# SHIELD_ENC28J60.net
KiCad netlist of a schematic drawn in Altium Designer
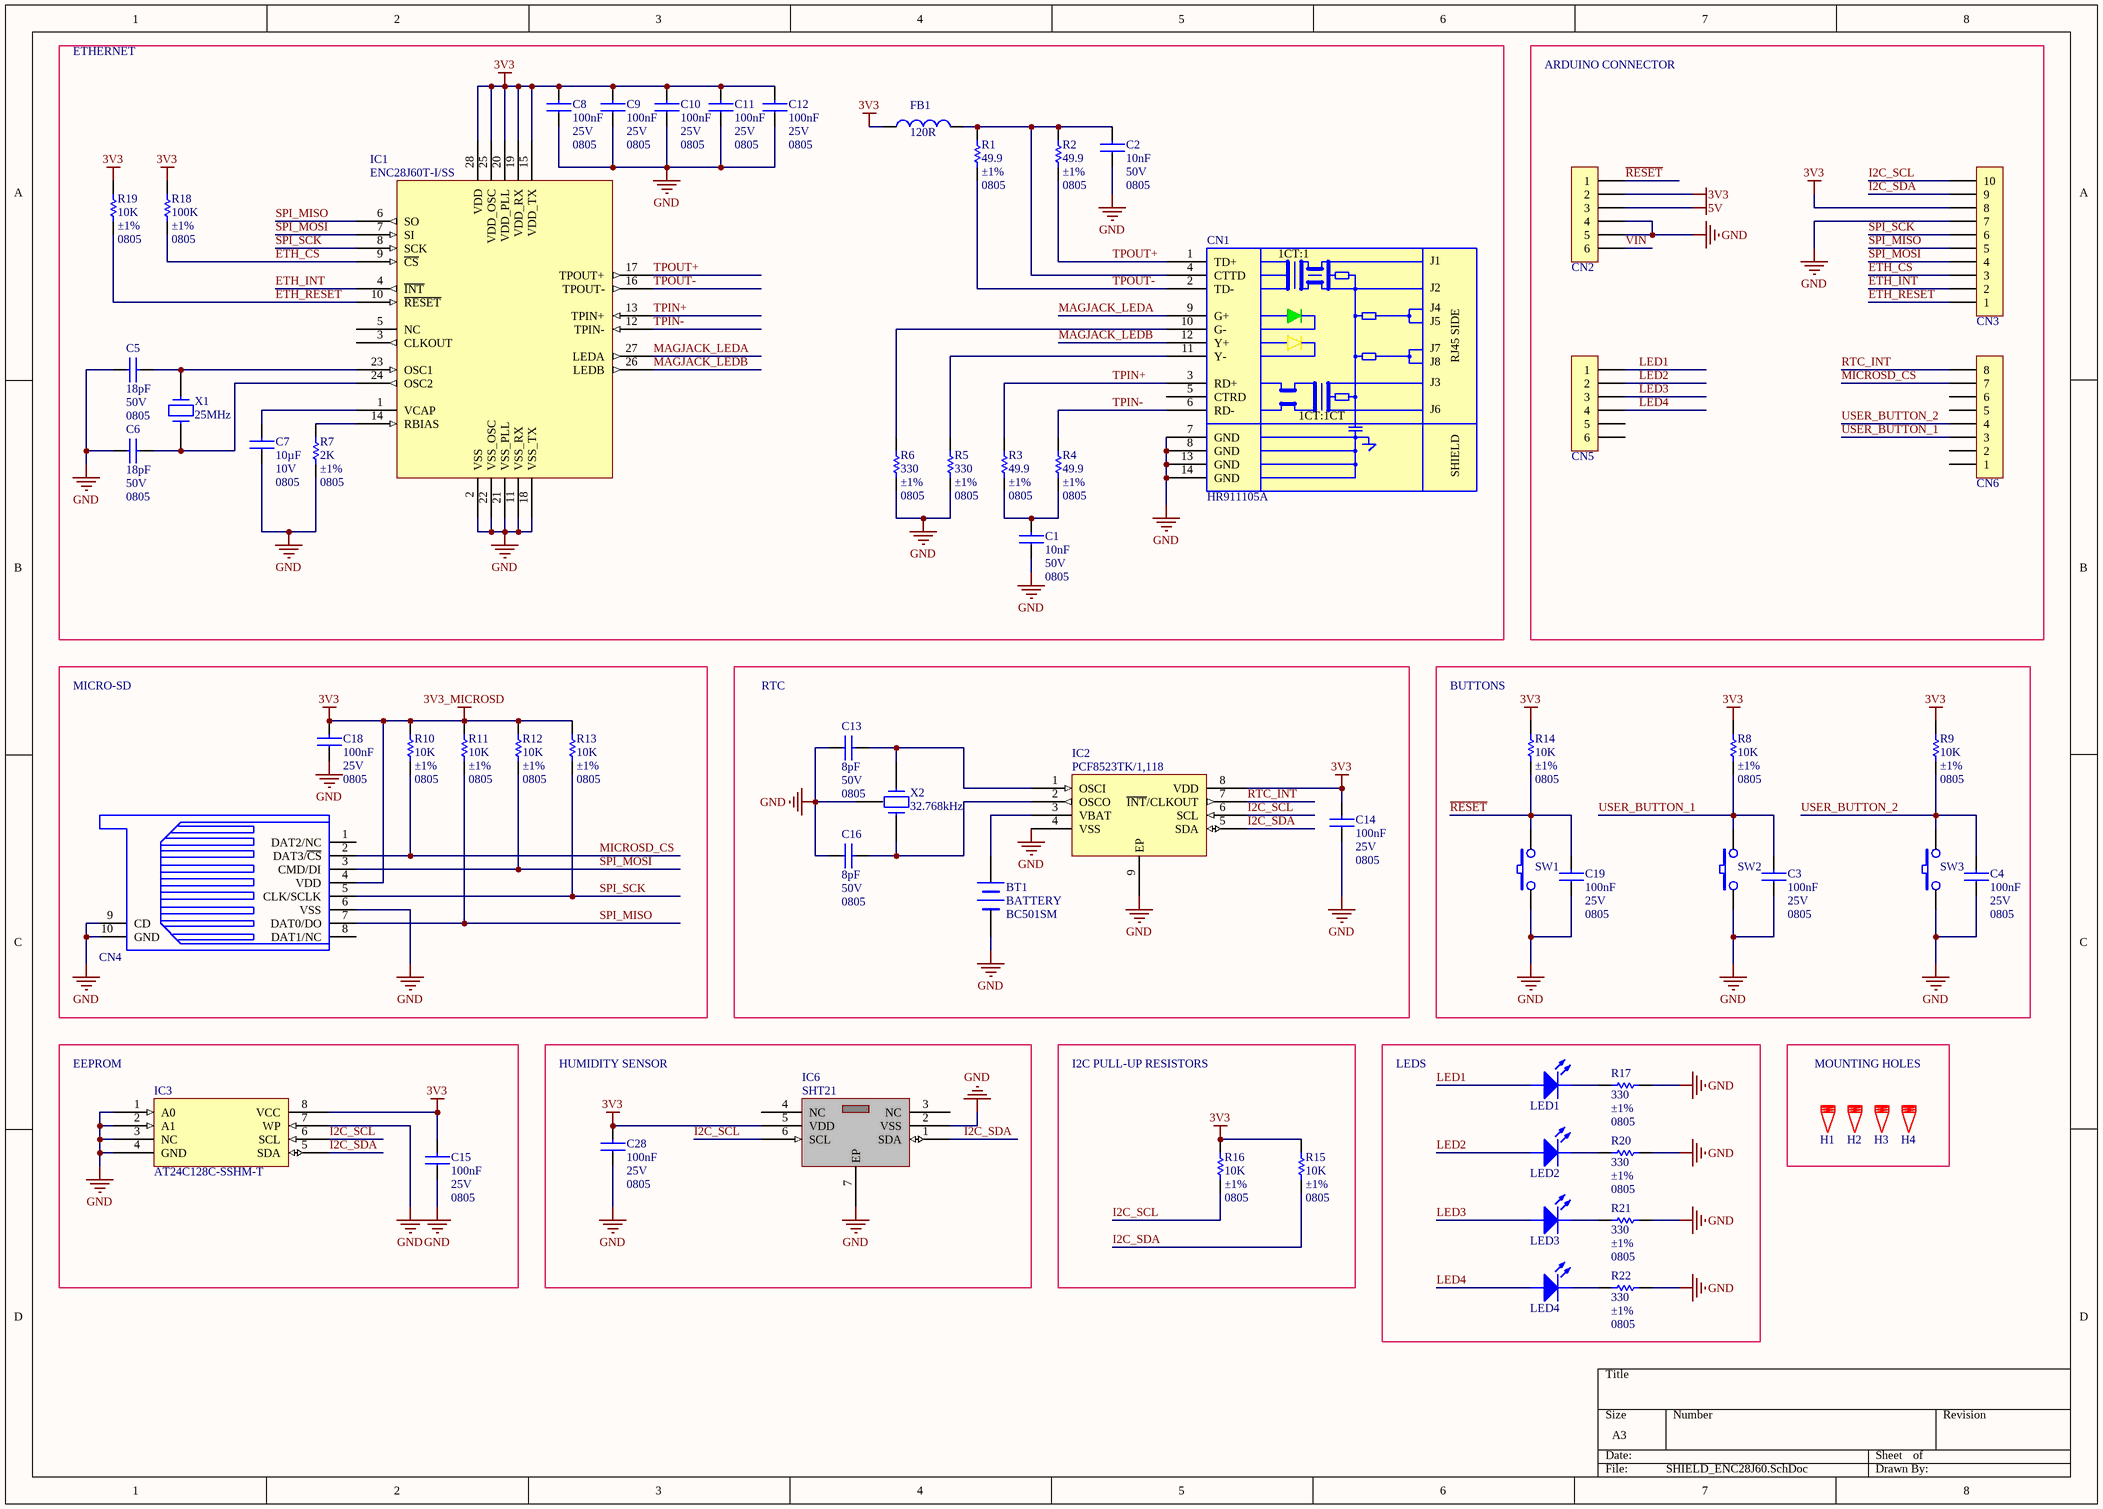
[diagram p0: SHIELD_ENC28J60.SchDoc]

(export (version "E")
  (design (tool "Eeschema 10.0.6"))
  (components
    (comp (ref "BT1")
      (value "BATTERY")
      (footprint "MPD_BC501SM")
      (description "HOLDER COIN CELL FOR CR1220 SMD")
      (fields
        (field (name "PART NUMBER") "SBAT00011")
        (field (name "MANUFACTURER PART NUMBER") "BC501SM")
        (field (name "VOLTAGE") "3V")
      )
      (libsource (lib "ComponentDatabase") (part "BATTERY"))
    )
    (comp (ref "C1")
      (value "CAP_NP")
      (footprint "CAPC2012X100N_EIA0805")
      (description "CAP CER 10000PF 50V X7R 0805")
      (fields
        (field (name "PART NUMBER") "SCAP00300085")
        (field (name "CAPACITANCE") "10nF")
        (field (name "VOLTAGE - RATED") "50V")
        (field (name "PACKAGE / CASE") "0805")
        (field (name "TOLERANCE") "±10%")
      )
      (libsource (lib "ComponentDatabase") (part "CAP_NP"))
    )
    (comp (ref "C2")
      (value "CAP_NP")
      (footprint "CAPC2012X100N_EIA0805")
      (description "CAP CER 10000PF 50V X7R 0805")
      (fields
        (field (name "PART NUMBER") "SCAP00300085")
        (field (name "CAPACITANCE") "10nF")
        (field (name "VOLTAGE - RATED") "50V")
        (field (name "PACKAGE / CASE") "0805")
        (field (name "TOLERANCE") "±10%")
      )
      (libsource (lib "ComponentDatabase") (part "CAP_NP"))
    )
    (comp (ref "C3")
      (value "CAP_NP")
      (footprint "CAPC2012X100N_EIA0805")
      (description "CAP CER 0.1UF 25V X7R 0805")
      (fields
        (field (name "PART NUMBER") "SCAP00300093")
        (field (name "CAPACITANCE") "100nF")
        (field (name "VOLTAGE - RATED") "25V")
        (field (name "PACKAGE / CASE") "0805")
        (field (name "TOLERANCE") "±10%")
      )
      (libsource (lib "ComponentDatabase") (part "CAP_NP"))
    )
    (comp (ref "C4")
      (value "CAP_NP")
      (footprint "CAPC2012X100N_EIA0805")
      (description "CAP CER 0.1UF 25V X7R 0805")
      (fields
        (field (name "PART NUMBER") "SCAP00300093")
        (field (name "CAPACITANCE") "100nF")
        (field (name "VOLTAGE - RATED") "25V")
        (field (name "PACKAGE / CASE") "0805")
        (field (name "TOLERANCE") "±10%")
      )
      (libsource (lib "ComponentDatabase") (part "CAP_NP"))
    )
    (comp (ref "C5")
      (value "CAP_NP")
      (footprint "CAPC2012X100N_EIA0805")
      (description "CAP CER 18PF 50V NP0 0805")
      (fields
        (field (name "PART NUMBER") "SCAP00300040")
        (field (name "CAPACITANCE") "18pF")
        (field (name "VOLTAGE - RATED") "50V")
        (field (name "PACKAGE / CASE") "0805")
        (field (name "TOLERANCE") "±5%")
      )
      (libsource (lib "ComponentDatabase") (part "CAP_NP"))
    )
    (comp (ref "C6")
      (value "CAP_NP")
      (footprint "CAPC2012X100N_EIA0805")
      (description "CAP CER 18PF 50V NP0 0805")
      (fields
        (field (name "PART NUMBER") "SCAP00300040")
        (field (name "CAPACITANCE") "18pF")
        (field (name "VOLTAGE - RATED") "50V")
        (field (name "PACKAGE / CASE") "0805")
        (field (name "TOLERANCE") "±5%")
      )
      (libsource (lib "ComponentDatabase") (part "CAP_NP"))
    )
    (comp (ref "C7")
      (value "CAP_NP")
      (footprint "CAPC2012X100N_EIA0805")
      (description "CAP CER 10UF 10V X5R 0805")
      (fields
        (field (name "PART NUMBER") "SCAP00300106")
        (field (name "CAPACITANCE") "10µF")
        (field (name "VOLTAGE - RATED") "10V")
        (field (name "PACKAGE / CASE") "0805")
        (field (name "TOLERANCE") "±10%")
      )
      (libsource (lib "ComponentDatabase") (part "CAP_NP"))
    )
    (comp (ref "C8")
      (value "CAP_NP")
      (footprint "CAPC2012X100N_EIA0805")
      (description "CAP CER 0.1UF 25V X7R 0805")
      (fields
        (field (name "PART NUMBER") "SCAP00300093")
        (field (name "CAPACITANCE") "100nF")
        (field (name "VOLTAGE - RATED") "25V")
        (field (name "PACKAGE / CASE") "0805")
        (field (name "TOLERANCE") "±10%")
      )
      (libsource (lib "ComponentDatabase") (part "CAP_NP"))
    )
    (comp (ref "C9")
      (value "CAP_NP")
      (footprint "CAPC2012X100N_EIA0805")
      (description "CAP CER 0.1UF 25V X7R 0805")
      (fields
        (field (name "PART NUMBER") "SCAP00300093")
        (field (name "CAPACITANCE") "100nF")
        (field (name "VOLTAGE - RATED") "25V")
        (field (name "PACKAGE / CASE") "0805")
        (field (name "TOLERANCE") "±10%")
      )
      (libsource (lib "ComponentDatabase") (part "CAP_NP"))
    )
    (comp (ref "C10")
      (value "CAP_NP")
      (footprint "CAPC2012X100N_EIA0805")
      (description "CAP CER 0.1UF 25V X7R 0805")
      (fields
        (field (name "PART NUMBER") "SCAP00300093")
        (field (name "CAPACITANCE") "100nF")
        (field (name "VOLTAGE - RATED") "25V")
        (field (name "PACKAGE / CASE") "0805")
        (field (name "TOLERANCE") "±10%")
      )
      (libsource (lib "ComponentDatabase") (part "CAP_NP"))
    )
    (comp (ref "C11")
      (value "CAP_NP")
      (footprint "CAPC2012X100N_EIA0805")
      (description "CAP CER 0.1UF 25V X7R 0805")
      (fields
        (field (name "PART NUMBER") "SCAP00300093")
        (field (name "CAPACITANCE") "100nF")
        (field (name "VOLTAGE - RATED") "25V")
        (field (name "PACKAGE / CASE") "0805")
        (field (name "TOLERANCE") "±10%")
      )
      (libsource (lib "ComponentDatabase") (part "CAP_NP"))
    )
    (comp (ref "C12")
      (value "CAP_NP")
      (footprint "CAPC2012X100N_EIA0805")
      (description "CAP CER 0.1UF 25V X7R 0805")
      (fields
        (field (name "PART NUMBER") "SCAP00300093")
        (field (name "CAPACITANCE") "100nF")
        (field (name "VOLTAGE - RATED") "25V")
        (field (name "PACKAGE / CASE") "0805")
        (field (name "TOLERANCE") "±10%")
      )
      (libsource (lib "ComponentDatabase") (part "CAP_NP"))
    )
    (comp (ref "C13")
      (value "CAP_NP")
      (footprint "CAPC2012X100N_EIA0805")
      (description "CAP CER 8PF 50V NP0 0805")
      (fields
        (field (name "PART NUMBER") "SCAP00300030")
        (field (name "CAPACITANCE") "8pF")
        (field (name "VOLTAGE - RATED") "50V")
        (field (name "PACKAGE / CASE") "0805")
        (field (name "TOLERANCE") "±0.25pF")
      )
      (libsource (lib "ComponentDatabase") (part "CAP_NP"))
    )
    (comp (ref "C14")
      (value "CAP_NP")
      (footprint "CAPC2012X100N_EIA0805")
      (description "CAP CER 0.1UF 25V X7R 0805")
      (fields
        (field (name "PART NUMBER") "SCAP00300093")
        (field (name "CAPACITANCE") "100nF")
        (field (name "VOLTAGE - RATED") "25V")
        (field (name "PACKAGE / CASE") "0805")
        (field (name "TOLERANCE") "±10%")
      )
      (libsource (lib "ComponentDatabase") (part "CAP_NP"))
    )
    (comp (ref "C15")
      (value "CAP_NP")
      (footprint "CAPC2012X100N_EIA0805")
      (description "CAP CER 0.1UF 25V X7R 0805")
      (fields
        (field (name "PART NUMBER") "SCAP00300093")
        (field (name "CAPACITANCE") "100nF")
        (field (name "VOLTAGE - RATED") "25V")
        (field (name "PACKAGE / CASE") "0805")
        (field (name "TOLERANCE") "±10%")
      )
      (libsource (lib "ComponentDatabase") (part "CAP_NP"))
    )
    (comp (ref "C16")
      (value "CAP_NP")
      (footprint "CAPC2012X100N_EIA0805")
      (description "CAP CER 8PF 50V NP0 0805")
      (fields
        (field (name "PART NUMBER") "SCAP00300030")
        (field (name "CAPACITANCE") "8pF")
        (field (name "VOLTAGE - RATED") "50V")
        (field (name "PACKAGE / CASE") "0805")
        (field (name "TOLERANCE") "±0.25pF")
      )
      (libsource (lib "ComponentDatabase") (part "CAP_NP"))
    )
    (comp (ref "C18")
      (value "CAP_NP")
      (footprint "CAPC2012X100N_EIA0805")
      (description "CAP CER 0.1UF 25V X7R 0805")
      (fields
        (field (name "PART NUMBER") "SCAP00300093")
        (field (name "CAPACITANCE") "100nF")
        (field (name "VOLTAGE - RATED") "25V")
        (field (name "PACKAGE / CASE") "0805")
        (field (name "TOLERANCE") "±10%")
      )
      (libsource (lib "ComponentDatabase") (part "CAP_NP"))
    )
    (comp (ref "C19")
      (value "CAP_NP")
      (footprint "CAPC2012X100N_EIA0805")
      (description "CAP CER 0.1UF 25V X7R 0805")
      (fields
        (field (name "PART NUMBER") "SCAP00300093")
        (field (name "CAPACITANCE") "100nF")
        (field (name "VOLTAGE - RATED") "25V")
        (field (name "PACKAGE / CASE") "0805")
        (field (name "TOLERANCE") "±10%")
      )
      (libsource (lib "ComponentDatabase") (part "CAP_NP"))
    )
    (comp (ref "C28")
      (value "CAP_NP")
      (footprint "CAPC2012X100N_EIA0805")
      (description "CAP CER 0.1UF 25V X7R 0805")
      (fields
        (field (name "PART NUMBER") "SCAP00300093")
        (field (name "CAPACITANCE") "100nF")
        (field (name "TOLERANCE") "±10%")
        (field (name "VOLTAGE - RATED") "25V")
        (field (name "PACKAGE / CASE") "0805")
      )
      (libsource (lib "ComponentDatabase") (part "CAP_NP"))
    )
    (comp (ref "CN1")
      (value "HR911105A")
      (footprint "[HANRUN]HR911105A")
      (description "CONN MAGJACK 1PORT 100 BASE-T")
      (fields (field (name "PART NUMBER") "SCON00127"))
      (libsource (lib "ComponentDatabase") (part "HR911105A"))
    )
    (comp (ref "CN2")
      (value "HDR_1X6")
      (footprint "HDRFV6W70P254_1X6_1524X254X1118P")
      (description "CONN ARDUINO HEADER .0100\" 6POS")
      (fields (field (name "PART NUMBER") "SCON00124"))
      (libsource (lib "ComponentDatabase") (part "HDR_1X6"))
    )
    (comp (ref "CN3")
      (value "HDR_1X10")
      (footprint "HDRFV10W70P254_1X10_2540X254X1118P")
      (description "CONN ARDUINO HEADER .0100\" 10POS")
      (fields (field (name "PART NUMBER") "SCON00126"))
      (libsource (lib "ComponentDatabase") (part "HDR_1X10"))
    )
    (comp (ref "CN4")
      (value "MICRO-SD")
      (footprint "MICRO-SD-SELF-EJECT")
      (description "CONN MICRO SD CARD PUSH-PUSH R/A")
      (fields (field (name "PART NUMBER") "SCON00094") (field (name "MANUFACTURER") "TransFlash"))
      (libsource (lib "ComponentDatabase") (part "MICRO-SD"))
    )
    (comp (ref "CN5")
      (value "HDR_1X6")
      (footprint "HDRFV6W70P254_1X6_1524X254X1118P")
      (description "CONN ARDUINO HEADER .0100\" 6POS")
      (fields (field (name "PART NUMBER") "SCON00124"))
      (libsource (lib "ComponentDatabase") (part "HDR_1X6"))
    )
    (comp (ref "CN6")
      (value "HDR_1X8")
      (footprint "HDRFV8W70P254_1X8_2032X254X1118P")
      (description "CONN ARDUINO HEADER .0100\" 8POS")
      (fields (field (name "PART NUMBER") "SCON00125"))
      (libsource (lib "ComponentDatabase") (part "HDR_1X8"))
    )
    (comp (ref "FB1")
      (value "BEAD")
      (footprint "FILC2012X100N_EIA0805")
      (description "FERRITE CHIP POWER 120 OHM SMD")
      (fields
        (field (name "PART NUMBER") "SFIL00005")
        (field (name "IMPEDANCE") "120R")
        (field (name "MANUFACTURER") "Laird-Signal Integrity Products")
      )
      (libsource (lib "ComponentDatabase") (part "BEAD"))
    )
    (comp (ref "H1")
      (value "HOLES")
      (footprint "HOLE_125MIL")
      (description "Holes")
      (fields (field (name "PART NUMBER") "SMSC00005"))
      (libsource (lib "ComponentDatabase") (part "HOLES"))
    )
    (comp (ref "H2")
      (value "HOLES")
      (footprint "HOLE_125MIL")
      (description "Holes")
      (fields (field (name "PART NUMBER") "SMSC00005"))
      (libsource (lib "ComponentDatabase") (part "HOLES"))
    )
    (comp (ref "H3")
      (value "HOLES")
      (footprint "HOLE_125MIL")
      (description "Holes")
      (fields (field (name "PART NUMBER") "SMSC00005"))
      (libsource (lib "ComponentDatabase") (part "HOLES"))
    )
    (comp (ref "H4")
      (value "HOLES")
      (footprint "HOLE_125MIL")
      (description "Holes")
      (fields (field (name "PART NUMBER") "SMSC00005"))
      (libsource (lib "ComponentDatabase") (part "HOLES"))
    )
    (comp (ref "IC1")
      (value "ENC28J60T-I/SS")
      (footprint "SOP65P780X200-28N_[MICROCHIP]SSOP28")
      (description "IC ETHERNET CTLR SPI 28SSOP")
      (fields
        (field (name "PART NUMBER") "SIC00131")
        (field (name "MANUFACTURER") "Microchip Technology")
        (field (name "MANUFACTURER PART NUMBER") "ENC28J60T-I/SS")
      )
      (libsource (lib "ComponentDatabase") (part "ENC28J60T-I/SS"))
    )
    (comp (ref "IC2")
      (value "PCF8523TK/1,118")
      (footprint "SON80P400X100_HS-9N_[NXP]SOT909-1")
      (description "IC RTC CLK/CALENDAR I2C 8-HVSON")
      (fields
        (field (name "PART NUMBER") "SIC00133")
        (field (name "MANUFACTURER PART NUMBER") "PCF8523TK/1,118")
        (field (name "MANUFACTURER") "NXP Semiconductors")
      )
      (libsource (lib "ComponentDatabase") (part "PCF8523TK/1,118"))
    )
    (comp (ref "IC3")
      (value "AT24C128")
      (footprint "SOIC127P600X175-8N")
      (description "IC EEPROM 128KBIT 1MHZ 8SOIC")
      (fields
        (field (name "PART NUMBER") "SMEM00014")
        (field (name "VOLTAGE") "1.7 V ~ 5.5 V")
        (field (name "MANUFACTURER PART NUMBER") "AT24C128C-SSHM-T")
      )
      (libsource (lib "ComponentDatabase") (part "AT24C128"))
    )
    (comp (ref "IC6")
      (value "SHT21")
      (footprint "SHT21")
      (description "HUMIDITY AND TEMPERATURE SENSOR")
      (fields
        (field (name "PART NUMBER") "SSEN00014")
        (field (name "VOLTAGE") "2.1 V ~ 3.6 V")
        (field (name "MANUFACTURER PART NUMBER") "SHT21")
      )
      (libsource (lib "ComponentDatabase") (part "SHT21"))
    )
    (comp (ref "LED1")
      (value "LED")
      (footprint "LEDC2012X70N_EIA0805_RED")
      (description "LED SUPER RED CLR THIN 0805 SMD")
      (fields (field (name "PART NUMBER") "SOPT00004") (field (name "MANUFACTURER") "Lite-On Inc"))
      (libsource (lib "ComponentDatabase") (part "LED"))
    )
    (comp (ref "LED2")
      (value "LED")
      (footprint "LEDC2012X70N_EIA0805_RED")
      (description "LED SUPER RED CLR THIN 0805 SMD")
      (fields (field (name "PART NUMBER") "SOPT00004") (field (name "MANUFACTURER") "Lite-On Inc"))
      (libsource (lib "ComponentDatabase") (part "LED"))
    )
    (comp (ref "LED3")
      (value "LED")
      (footprint "LEDC2012X70N_EIA0805_RED")
      (description "LED SUPER RED CLR THIN 0805 SMD")
      (fields (field (name "PART NUMBER") "SOPT00004") (field (name "MANUFACTURER") "Lite-On Inc"))
      (libsource (lib "ComponentDatabase") (part "LED"))
    )
    (comp (ref "LED4")
      (value "LED")
      (footprint "LEDC2012X70N_EIA0805_RED")
      (description "LED SUPER RED CLR THIN 0805 SMD")
      (fields (field (name "PART NUMBER") "SOPT00004") (field (name "MANUFACTURER") "Lite-On Inc"))
      (libsource (lib "ComponentDatabase") (part "LED"))
    )
    (comp (ref "R1")
      (value "RES")
      (footprint "RESC2013X65N_EIA0805")
      (description "RES SMD 49.9 OHM 1% 1/8W 0805")
      (fields
        (field (name "PART NUMBER") "SRES03030081")
        (field (name "RESISTANCE (OHM)") "49.9")
        (field (name "TOLERANCE") "±1%")
        (field (name "PACKAGE / CASE") "0805")
        (field (name "MANUFACTURER") "Samsung Electro-Mechanics America, Inc.")
      )
      (libsource (lib "ComponentDatabase") (part "RES"))
    )
    (comp (ref "R2")
      (value "RES")
      (footprint "RESC2013X65N_EIA0805")
      (description "RES SMD 49.9 OHM 1% 1/8W 0805")
      (fields
        (field (name "PART NUMBER") "SRES03030081")
        (field (name "RESISTANCE (OHM)") "49.9")
        (field (name "TOLERANCE") "±1%")
        (field (name "PACKAGE / CASE") "0805")
        (field (name "MANUFACTURER") "Samsung Electro-Mechanics America, Inc.")
      )
      (libsource (lib "ComponentDatabase") (part "RES"))
    )
    (comp (ref "R3")
      (value "RES")
      (footprint "RESC2013X65N_EIA0805")
      (description "RES SMD 49.9 OHM 1% 1/8W 0805")
      (fields
        (field (name "PART NUMBER") "SRES03030081")
        (field (name "RESISTANCE (OHM)") "49.9")
        (field (name "TOLERANCE") "±1%")
        (field (name "PACKAGE / CASE") "0805")
        (field (name "MANUFACTURER") "Samsung Electro-Mechanics America, Inc.")
      )
      (libsource (lib "ComponentDatabase") (part "RES"))
    )
    (comp (ref "R4")
      (value "RES")
      (footprint "RESC2013X65N_EIA0805")
      (description "RES SMD 49.9 OHM 1% 1/8W 0805")
      (fields
        (field (name "PART NUMBER") "SRES03030081")
        (field (name "RESISTANCE (OHM)") "49.9")
        (field (name "TOLERANCE") "±1%")
        (field (name "PACKAGE / CASE") "0805")
        (field (name "MANUFACTURER") "Samsung Electro-Mechanics America, Inc.")
      )
      (libsource (lib "ComponentDatabase") (part "RES"))
    )
    (comp (ref "R5")
      (value "RES")
      (footprint "RESC2013X65N_EIA0805")
      (description "RES SMD 330 OHM 1% 1/8W 0805")
      (fields
        (field (name "PART NUMBER") "SRES03010062")
        (field (name "RESISTANCE (OHM)") "330")
        (field (name "TOLERANCE") "±1%")
        (field (name "PACKAGE / CASE") "0805")
        (field (name "MANUFACTURER") "Yageo")
      )
      (libsource (lib "ComponentDatabase") (part "RES"))
    )
    (comp (ref "R6")
      (value "RES")
      (footprint "RESC2013X65N_EIA0805")
      (description "RES SMD 330 OHM 1% 1/8W 0805")
      (fields
        (field (name "PART NUMBER") "SRES03010062")
        (field (name "RESISTANCE (OHM)") "330")
        (field (name "TOLERANCE") "±1%")
        (field (name "PACKAGE / CASE") "0805")
        (field (name "MANUFACTURER") "Yageo")
      )
      (libsource (lib "ComponentDatabase") (part "RES"))
    )
    (comp (ref "R7")
      (value "RES")
      (footprint "RESC2013X65N_EIA0805")
      (description "RES SMD 2K OHM 1% 1/8W 0805")
      (fields
        (field (name "PART NUMBER") "SRES03010081")
        (field (name "RESISTANCE (OHM)") "2K")
        (field (name "TOLERANCE") "±1%")
        (field (name "PACKAGE / CASE") "0805")
        (field (name "MANUFACTURER") "Yageo")
      )
      (libsource (lib "ComponentDatabase") (part "RES"))
    )
    (comp (ref "R8")
      (value "RES")
      (footprint "RESC2013X65N_EIA0805")
      (description "RES SMD 10K OHM 1% 1/8W 0805")
      (fields
        (field (name "PART NUMBER") "SRES03010098")
        (field (name "RESISTANCE (OHM)") "10K")
        (field (name "TOLERANCE") "±1%")
        (field (name "PACKAGE / CASE") "0805")
        (field (name "MANUFACTURER") "Yageo")
      )
      (libsource (lib "ComponentDatabase") (part "RES"))
    )
    (comp (ref "R9")
      (value "RES")
      (footprint "RESC2013X65N_EIA0805")
      (description "RES SMD 10K OHM 1% 1/8W 0805")
      (fields
        (field (name "PART NUMBER") "SRES03010098")
        (field (name "RESISTANCE (OHM)") "10K")
        (field (name "TOLERANCE") "±1%")
        (field (name "PACKAGE / CASE") "0805")
        (field (name "MANUFACTURER") "Yageo")
      )
      (libsource (lib "ComponentDatabase") (part "RES"))
    )
    (comp (ref "R10")
      (value "RES")
      (footprint "RESC2013X65N_EIA0805")
      (description "RES SMD 10K OHM 1% 1/8W 0805")
      (fields
        (field (name "PART NUMBER") "SRES03010098")
        (field (name "RESISTANCE (OHM)") "10K")
        (field (name "TOLERANCE") "±1%")
        (field (name "PACKAGE / CASE") "0805")
        (field (name "MANUFACTURER") "Yageo")
      )
      (libsource (lib "ComponentDatabase") (part "RES"))
    )
    (comp (ref "R11")
      (value "RES")
      (footprint "RESC2013X65N_EIA0805")
      (description "RES SMD 10K OHM 1% 1/8W 0805")
      (fields
        (field (name "PART NUMBER") "SRES03010098")
        (field (name "RESISTANCE (OHM)") "10K")
        (field (name "TOLERANCE") "±1%")
        (field (name "PACKAGE / CASE") "0805")
        (field (name "MANUFACTURER") "Yageo")
      )
      (libsource (lib "ComponentDatabase") (part "RES"))
    )
    (comp (ref "R12")
      (value "RES")
      (footprint "RESC2013X65N_EIA0805")
      (description "RES SMD 10K OHM 1% 1/8W 0805")
      (fields
        (field (name "PART NUMBER") "SRES03010098")
        (field (name "RESISTANCE (OHM)") "10K")
        (field (name "TOLERANCE") "±1%")
        (field (name "PACKAGE / CASE") "0805")
        (field (name "MANUFACTURER") "Yageo")
      )
      (libsource (lib "ComponentDatabase") (part "RES"))
    )
    (comp (ref "R13")
      (value "RES")
      (footprint "RESC2013X65N_EIA0805")
      (description "RES SMD 10K OHM 1% 1/8W 0805")
      (fields
        (field (name "PART NUMBER") "SRES03010098")
        (field (name "RESISTANCE (OHM)") "10K")
        (field (name "TOLERANCE") "±1%")
        (field (name "PACKAGE / CASE") "0805")
        (field (name "MANUFACTURER") "Yageo")
      )
      (libsource (lib "ComponentDatabase") (part "RES"))
    )
    (comp (ref "R14")
      (value "RES")
      (footprint "RESC2013X65N_EIA0805")
      (description "RES SMD 10K OHM 1% 1/8W 0805")
      (fields
        (field (name "PART NUMBER") "SRES03010098")
        (field (name "RESISTANCE (OHM)") "10K")
        (field (name "TOLERANCE") "±1%")
        (field (name "PACKAGE / CASE") "0805")
        (field (name "MANUFACTURER") "Yageo")
      )
      (libsource (lib "ComponentDatabase") (part "RES"))
    )
    (comp (ref "R15")
      (value "RES")
      (footprint "RESC2013X65N_EIA0805")
      (description "RES SMD 10K OHM 1% 1/8W 0805")
      (fields
        (field (name "PART NUMBER") "SRES03010098")
        (field (name "RESISTANCE (OHM)") "10K")
        (field (name "TOLERANCE") "±1%")
        (field (name "PACKAGE / CASE") "0805")
        (field (name "MANUFACTURER") "Yageo")
      )
      (libsource (lib "ComponentDatabase") (part "RES"))
    )
    (comp (ref "R16")
      (value "RES")
      (footprint "RESC2013X65N_EIA0805")
      (description "RES SMD 10K OHM 1% 1/8W 0805")
      (fields
        (field (name "PART NUMBER") "SRES03010098")
        (field (name "RESISTANCE (OHM)") "10K")
        (field (name "TOLERANCE") "±1%")
        (field (name "PACKAGE / CASE") "0805")
        (field (name "MANUFACTURER") "Yageo")
      )
      (libsource (lib "ComponentDatabase") (part "RES"))
    )
    (comp (ref "R17")
      (value "RES")
      (footprint "RESC2013X65N_EIA0805")
      (description "RES SMD 330 OHM 1% 1/8W 0805")
      (fields
        (field (name "PART NUMBER") "SRES03010062")
        (field (name "RESISTANCE (OHM)") "330")
        (field (name "TOLERANCE") "±1%")
        (field (name "PACKAGE / CASE") "0805")
        (field (name "MANUFACTURER") "Yageo")
      )
      (libsource (lib "ComponentDatabase") (part "RES"))
    )
    (comp (ref "R18")
      (value "RES")
      (footprint "RESC2013X65N_EIA0805")
      (description "RES SMD 100K OHM 1% 1/8W 0805")
      (fields
        (field (name "PART NUMBER") "SRES03010122")
        (field (name "RESISTANCE (OHM)") "100K")
        (field (name "TOLERANCE") "±1%")
        (field (name "PACKAGE / CASE") "0805")
        (field (name "MANUFACTURER") "Yageo")
      )
      (libsource (lib "ComponentDatabase") (part "RES"))
    )
    (comp (ref "R19")
      (value "RES")
      (footprint "RESC2013X65N_EIA0805")
      (description "RES SMD 10K OHM 1% 1/8W 0805")
      (fields
        (field (name "PART NUMBER") "SRES03010098")
        (field (name "RESISTANCE (OHM)") "10K")
        (field (name "TOLERANCE") "±1%")
        (field (name "PACKAGE / CASE") "0805")
        (field (name "MANUFACTURER") "Yageo")
      )
      (libsource (lib "ComponentDatabase") (part "RES"))
    )
    (comp (ref "R20")
      (value "RES")
      (footprint "RESC2013X65N_EIA0805")
      (description "RES SMD 330 OHM 1% 1/8W 0805")
      (fields
        (field (name "PART NUMBER") "SRES03010062")
        (field (name "RESISTANCE (OHM)") "330")
        (field (name "TOLERANCE") "±1%")
        (field (name "PACKAGE / CASE") "0805")
        (field (name "MANUFACTURER") "Yageo")
      )
      (libsource (lib "ComponentDatabase") (part "RES"))
    )
    (comp (ref "R21")
      (value "RES")
      (footprint "RESC2013X65N_EIA0805")
      (description "RES SMD 330 OHM 1% 1/8W 0805")
      (fields
        (field (name "PART NUMBER") "SRES03010062")
        (field (name "RESISTANCE (OHM)") "330")
        (field (name "TOLERANCE") "±1%")
        (field (name "PACKAGE / CASE") "0805")
        (field (name "MANUFACTURER") "Yageo")
      )
      (libsource (lib "ComponentDatabase") (part "RES"))
    )
    (comp (ref "R22")
      (value "RES")
      (footprint "RESC2013X65N_EIA0805")
      (description "RES SMD 330 OHM 1% 1/8W 0805")
      (fields
        (field (name "PART NUMBER") "SRES03010062")
        (field (name "RESISTANCE (OHM)") "330")
        (field (name "TOLERANCE") "±1%")
        (field (name "PACKAGE / CASE") "0805")
        (field (name "MANUFACTURER") "Yageo")
      )
      (libsource (lib "ComponentDatabase") (part "RES"))
    )
    (comp (ref "SW1")
      (value "SWITCH_TACTILE_2PIN")
      (footprint "C&K_RS-282G05A3-SM_RT")
      (description "SWITCH TACTILE SPST-NO 0.05A 12V")
      (fields (field (name "PART NUMBER") "SSWI00022") (field (name "VOLTAGE") "12VDC"))
      (libsource (lib "ComponentDatabase") (part "SWITCH_TACTILE_2PIN"))
    )
    (comp (ref "SW2")
      (value "SWITCH_TACTILE_2PIN")
      (footprint "C&K_RS-282G05A3-SM_RT")
      (description "SWITCH TACTILE SPST-NO 0.05A 12V")
      (fields (field (name "PART NUMBER") "SSWI00022") (field (name "VOLTAGE") "12VDC"))
      (libsource (lib "ComponentDatabase") (part "SWITCH_TACTILE_2PIN"))
    )
    (comp (ref "SW3")
      (value "SWITCH_TACTILE_2PIN")
      (footprint "C&K_RS-282G05A3-SM_RT")
      (description "SWITCH TACTILE SPST-NO 0.05A 12V")
      (fields (field (name "PART NUMBER") "SSWI00022") (field (name "VOLTAGE") "12VDC"))
      (libsource (lib "ComponentDatabase") (part "SWITCH_TACTILE_2PIN"))
    )
    (comp (ref "X1")
      (value "25MHz")
      (footprint "HC-49/US")
      (description "CRYSTAL 25.0000MHZ 18PF T/H")
      (fields (field (name "PART NUMBER") "SCRY00016") (field (name "MANUFACTURER") "CTS-Frequency Controls"))
      (libsource (lib "ComponentDatabase") (part "CRYSTAL"))
    )
    (comp (ref "X2")
      (value "32.768kHz")
      (footprint "32.768_DIP")
      (description "CRYSTAL 32.768KHZ 6PF THRU")
      (fields (field (name "PART NUMBER") "SCRY00009") (field (name "MANUFACTURER") "Seiko Instruments"))
      (libsource (lib "ComponentDatabase") (part "CRYSTAL_32K"))
    )
  )
  (nets
    (net (code "1") (name "/ETH_CS") (class "Default")
      (node (ref "CN3") (pin "3") (pinfunction "3_3") (pintype "passive"))
      (node (ref "IC1") (pin "9") (pinfunction "~{CS}_9") (pintype "input"))
      (node (ref "R18") (pin "2") (pinfunction "2_2") (pintype "passive"))
    )
    (net (code "2") (name "/ETH_INT") (class "Default")
      (node (ref "CN3") (pin "2") (pinfunction "2_2") (pintype "passive"))
      (node (ref "IC1") (pin "4") (pinfunction "~{INT}_4") (pintype "output"))
    )
    (net (code "3") (name "/ETH_RESET") (class "Default")
      (node (ref "CN3") (pin "1") (pinfunction "1_1") (pintype "passive"))
      (node (ref "IC1") (pin "10") (pinfunction "~{RESET}_10") (pintype "input"))
      (node (ref "R19") (pin "2") (pinfunction "2_2") (pintype "passive"))
    )
    (net (code "4") (name "/I2C_SCL") (class "Default")
      (node (ref "CN3") (pin "10") (pinfunction "10_10") (pintype "passive"))
      (node (ref "IC2") (pin "6") (pinfunction "SCL_6") (pintype "input"))
      (node (ref "IC3") (pin "6") (pinfunction "SCL_6") (pintype "input"))
      (node (ref "IC6") (pin "6") (pinfunction "SCL_6") (pintype "input"))
      (node (ref "R16") (pin "2") (pinfunction "2_2") (pintype "passive"))
    )
    (net (code "5") (name "/I2C_SDA") (class "Default")
      (node (ref "CN3") (pin "9") (pinfunction "9_9") (pintype "passive"))
      (node (ref "IC2") (pin "5") (pinfunction "SDA_5") (pintype "bidirectional"))
      (node (ref "IC3") (pin "5") (pinfunction "SDA_5") (pintype "bidirectional"))
      (node (ref "IC6") (pin "1") (pinfunction "SDA_1") (pintype "bidirectional"))
      (node (ref "R15") (pin "2") (pinfunction "2_2") (pintype "passive"))
    )
    (net (code "6") (name "/LED1") (class "Default")
      (node (ref "CN5") (pin "1") (pinfunction "1_1") (pintype "passive"))
      (node (ref "LED1") (pin "2") (pinfunction "2_2") (pintype "passive"))
    )
    (net (code "7") (name "/LED2") (class "Default")
      (node (ref "CN5") (pin "2") (pinfunction "2_2") (pintype "passive"))
      (node (ref "LED2") (pin "2") (pinfunction "2_2") (pintype "passive"))
    )
    (net (code "8") (name "/LED3") (class "Default")
      (node (ref "CN5") (pin "3") (pinfunction "3_3") (pintype "passive"))
      (node (ref "LED3") (pin "2") (pinfunction "2_2") (pintype "passive"))
    )
    (net (code "9") (name "/LED4") (class "Default")
      (node (ref "CN5") (pin "4") (pinfunction "4_4") (pintype "passive"))
      (node (ref "LED4") (pin "2") (pinfunction "2_2") (pintype "passive"))
    )
    (net (code "10") (name "/MAGJACK_LEDA") (class "Default")
      (node (ref "CN1") (pin "9") (pinfunction "G+_9") (pintype "passive"))
      (node (ref "IC1") (pin "27") (pinfunction "LEDA_27") (pintype "output"))
    )
    (net (code "11") (name "/MAGJACK_LEDB") (class "Default")
      (node (ref "CN1") (pin "12") (pinfunction "Y+_12") (pintype "passive"))
      (node (ref "IC1") (pin "26") (pinfunction "LEDB_26") (pintype "output"))
    )
    (net (code "12") (name "/MICROSD_CS") (class "Default")
      (node (ref "CN4") (pin "2") (pinfunction "DAT3/~{CS}_2") (pintype "passive"))
      (node (ref "CN6") (pin "7") (pinfunction "7_7") (pintype "passive"))
      (node (ref "R10") (pin "2") (pinfunction "2_2") (pintype "passive"))
    )
    (net (code "13") (name "/RTC_INT") (class "Default")
      (node (ref "CN6") (pin "8") (pinfunction "8_8") (pintype "passive"))
      (node (ref "IC2") (pin "7") (pinfunction "~{INT}/CLKOUT_7") (pintype "output"))
    )
    (net (code "14") (name "/SPI_MISO") (class "Default")
      (node (ref "CN3") (pin "5") (pinfunction "5_5") (pintype "passive"))
      (node (ref "CN4") (pin "7") (pinfunction "DAT0/DO_7") (pintype "passive"))
      (node (ref "IC1") (pin "6") (pinfunction "SO_6") (pintype "output"))
      (node (ref "R11") (pin "2") (pinfunction "2_2") (pintype "passive"))
    )
    (net (code "15") (name "/SPI_MOSI") (class "Default")
      (node (ref "CN3") (pin "4") (pinfunction "4_4") (pintype "passive"))
      (node (ref "CN4") (pin "3") (pinfunction "CMD/DI_3") (pintype "passive"))
      (node (ref "IC1") (pin "7") (pinfunction "SI_7") (pintype "input"))
      (node (ref "R12") (pin "2") (pinfunction "2_2") (pintype "passive"))
    )
    (net (code "16") (name "/SPI_SCK") (class "Default")
      (node (ref "CN3") (pin "6") (pinfunction "6_6") (pintype "passive"))
      (node (ref "CN4") (pin "5") (pinfunction "CLK/SCLK_5") (pintype "passive"))
      (node (ref "IC1") (pin "8") (pinfunction "SCK_8") (pintype "input"))
      (node (ref "R13") (pin "2") (pinfunction "2_2") (pintype "passive"))
    )
    (net (code "17") (name "/TPIN+") (class "Default")
      (node (ref "CN1") (pin "3") (pinfunction "RD+_3") (pintype "passive"))
      (node (ref "IC1") (pin "13") (pinfunction "TPIN+_13") (pintype "input"))
      (node (ref "R3") (pin "1") (pinfunction "1_1") (pintype "passive"))
    )
    (net (code "18") (name "/TPIN-") (class "Default")
      (node (ref "CN1") (pin "6") (pinfunction "RD-_6") (pintype "passive"))
      (node (ref "IC1") (pin "12") (pinfunction "TPIN-_12") (pintype "input"))
      (node (ref "R4") (pin "1") (pinfunction "1_1") (pintype "passive"))
    )
    (net (code "19") (name "/TPOUT+") (class "Default")
      (node (ref "CN1") (pin "1") (pinfunction "TD+_1") (pintype "passive"))
      (node (ref "IC1") (pin "17") (pinfunction "TPOUT+_17") (pintype "output"))
      (node (ref "R2") (pin "2") (pinfunction "2_2") (pintype "passive"))
    )
    (net (code "20") (name "/TPOUT-") (class "Default")
      (node (ref "CN1") (pin "2") (pinfunction "TD-_2") (pintype "passive"))
      (node (ref "IC1") (pin "16") (pinfunction "TPOUT-_16") (pintype "output"))
      (node (ref "R1") (pin "2") (pinfunction "2_2") (pintype "passive"))
    )
    (net (code "21") (name "/USER_BUTTON_1") (class "Default")
      (node (ref "C3") (pin "2") (pinfunction "2_2") (pintype "passive"))
      (node (ref "CN6") (pin "3") (pinfunction "3_3") (pintype "passive"))
      (node (ref "R8") (pin "2") (pinfunction "2_2") (pintype "passive"))
      (node (ref "SW2") (pin "2") (pinfunction "2_2") (pintype "passive"))
    )
    (net (code "22") (name "/USER_BUTTON_2") (class "Default")
      (node (ref "C4") (pin "2") (pinfunction "2_2") (pintype "passive"))
      (node (ref "CN6") (pin "4") (pinfunction "4_4") (pintype "passive"))
      (node (ref "R9") (pin "2") (pinfunction "2_2") (pintype "passive"))
      (node (ref "SW3") (pin "2") (pinfunction "2_2") (pintype "passive"))
    )
    (net (code "23") (name "/VIN") (class "Default")
      (node (ref "CN2") (pin "6") (pinfunction "6_6") (pintype "passive"))
    )
    (net (code "24") (name "/~{RESET}") (class "Default")
      (node (ref "C19") (pin "2") (pinfunction "2_2") (pintype "passive"))
      (node (ref "CN2") (pin "1") (pinfunction "1_1") (pintype "passive"))
      (node (ref "R14") (pin "2") (pinfunction "2_2") (pintype "passive"))
      (node (ref "SW1") (pin "2") (pinfunction "2_2") (pintype "passive"))
    )
    (net (code "25") (name "3V3") (class "Default")
      (node (ref "C10") (pin "2") (pinfunction "2_2") (pintype "passive"))
      (node (ref "C11") (pin "2") (pinfunction "2_2") (pintype "passive"))
      (node (ref "C12") (pin "2") (pinfunction "2_2") (pintype "passive"))
      (node (ref "C14") (pin "2") (pinfunction "2_2") (pintype "passive"))
      (node (ref "C15") (pin "2") (pinfunction "2_2") (pintype "passive"))
      (node (ref "C18") (pin "2") (pinfunction "2_2") (pintype "passive"))
      (node (ref "C28") (pin "2") (pinfunction "2_2") (pintype "passive"))
      (node (ref "C8") (pin "2") (pinfunction "2_2") (pintype "passive"))
      (node (ref "C9") (pin "2") (pinfunction "2_2") (pintype "passive"))
      (node (ref "CN2") (pin "2") (pinfunction "2_2") (pintype "passive"))
      (node (ref "CN3") (pin "8") (pinfunction "8_8") (pintype "passive"))
      (node (ref "CN4") (pin "4") (pinfunction "VDD_4") (pintype "passive"))
      (node (ref "FB1") (pin "1") (pinfunction "1_1") (pintype "passive"))
      (node (ref "IC1") (pin "15") (pinfunction "VDD_TX_15") (pintype "power_in"))
      (node (ref "IC1") (pin "19") (pinfunction "VDD_RX_19") (pintype "power_in"))
      (node (ref "IC1") (pin "20") (pinfunction "VDD_PLL_20") (pintype "power_in"))
      (node (ref "IC1") (pin "25") (pinfunction "VDD_OSC_25") (pintype "power_in"))
      (node (ref "IC1") (pin "28") (pinfunction "VDD_28") (pintype "power_in"))
      (node (ref "IC2") (pin "8") (pinfunction "VDD_8") (pintype "power_in"))
      (node (ref "IC3") (pin "8") (pinfunction "VCC_8") (pintype "power_in"))
      (node (ref "IC6") (pin "5") (pinfunction "VDD_5") (pintype "power_in"))
      (node (ref "R10") (pin "1") (pinfunction "1_1") (pintype "passive"))
      (node (ref "R11") (pin "1") (pinfunction "1_1") (pintype "passive"))
      (node (ref "R12") (pin "1") (pinfunction "1_1") (pintype "passive"))
      (node (ref "R13") (pin "1") (pinfunction "1_1") (pintype "passive"))
      (node (ref "R14") (pin "1") (pinfunction "1_1") (pintype "passive"))
      (node (ref "R15") (pin "1") (pinfunction "1_1") (pintype "passive"))
      (node (ref "R16") (pin "1") (pinfunction "1_1") (pintype "passive"))
      (node (ref "R18") (pin "1") (pinfunction "1_1") (pintype "passive"))
      (node (ref "R19") (pin "1") (pinfunction "1_1") (pintype "passive"))
      (node (ref "R8") (pin "1") (pinfunction "1_1") (pintype "passive"))
      (node (ref "R9") (pin "1") (pinfunction "1_1") (pintype "passive"))
    )
    (net (code "26") (name "5V") (class "Default")
      (node (ref "CN2") (pin "3") (pinfunction "3_3") (pintype "passive"))
    )
    (net (code "27") (name "GND") (class "Default")
      (node (ref "BT1") (pin "2") (pinfunction "-_2") (pintype "passive"))
      (node (ref "C1") (pin "1") (pinfunction "1_1") (pintype "passive"))
      (node (ref "C10") (pin "1") (pinfunction "1_1") (pintype "passive"))
      (node (ref "C11") (pin "1") (pinfunction "1_1") (pintype "passive"))
      (node (ref "C12") (pin "1") (pinfunction "1_1") (pintype "passive"))
      (node (ref "C13") (pin "1") (pinfunction "1_1") (pintype "passive"))
      (node (ref "C14") (pin "1") (pinfunction "1_1") (pintype "passive"))
      (node (ref "C15") (pin "1") (pinfunction "1_1") (pintype "passive"))
      (node (ref "C16") (pin "1") (pinfunction "1_1") (pintype "passive"))
      (node (ref "C18") (pin "1") (pinfunction "1_1") (pintype "passive"))
      (node (ref "C19") (pin "1") (pinfunction "1_1") (pintype "passive"))
      (node (ref "C2") (pin "1") (pinfunction "1_1") (pintype "passive"))
      (node (ref "C28") (pin "1") (pinfunction "1_1") (pintype "passive"))
      (node (ref "C3") (pin "1") (pinfunction "1_1") (pintype "passive"))
      (node (ref "C4") (pin "1") (pinfunction "1_1") (pintype "passive"))
      (node (ref "C5") (pin "1") (pinfunction "1_1") (pintype "passive"))
      (node (ref "C6") (pin "1") (pinfunction "1_1") (pintype "passive"))
      (node (ref "C7") (pin "1") (pinfunction "1_1") (pintype "passive"))
      (node (ref "C8") (pin "1") (pinfunction "1_1") (pintype "passive"))
      (node (ref "C9") (pin "1") (pinfunction "1_1") (pintype "passive"))
      (node (ref "CN1") (pin "13") (pinfunction "GND_13") (pintype "power_in"))
      (node (ref "CN1") (pin "14") (pinfunction "GND_14") (pintype "power_in"))
      (node (ref "CN1") (pin "7") (pinfunction "GND_7") (pintype "power_in"))
      (node (ref "CN1") (pin "8") (pinfunction "GND_8") (pintype "power_in"))
      (node (ref "CN2") (pin "4") (pinfunction "4_4") (pintype "passive"))
      (node (ref "CN2") (pin "5") (pinfunction "5_5") (pintype "passive"))
      (node (ref "CN3") (pin "7") (pinfunction "7_7") (pintype "passive"))
      (node (ref "CN4") (pin "10") (pinfunction "GND_10") (pintype "passive"))
      (node (ref "CN4") (pin "6") (pinfunction "VSS_6") (pintype "passive"))
      (node (ref "CN4") (pin "9") (pinfunction "CD_9") (pintype "passive"))
      (node (ref "IC1") (pin "11") (pinfunction "VSS_RX_11") (pintype "power_in"))
      (node (ref "IC1") (pin "18") (pinfunction "VSS_TX_18") (pintype "power_in"))
      (node (ref "IC1") (pin "2") (pinfunction "VSS_2") (pintype "power_in"))
      (node (ref "IC1") (pin "21") (pinfunction "VSS_PLL_21") (pintype "power_in"))
      (node (ref "IC1") (pin "22") (pinfunction "VSS_OSC_22") (pintype "power_in"))
      (node (ref "IC2") (pin "4") (pinfunction "VSS_4") (pintype "power_in"))
      (node (ref "IC2") (pin "9") (pinfunction "EP_9") (pintype "passive"))
      (node (ref "IC3") (pin "1") (pinfunction "A0_1") (pintype "input"))
      (node (ref "IC3") (pin "2") (pinfunction "A1_2") (pintype "input"))
      (node (ref "IC3") (pin "3") (pinfunction "NC_3") (pintype "passive"))
      (node (ref "IC3") (pin "4") (pinfunction "GND_4") (pintype "power_in"))
      (node (ref "IC3") (pin "7") (pinfunction "WP_7") (pintype "input"))
      (node (ref "IC6") (pin "2") (pinfunction "VSS_2") (pintype "power_in"))
      (node (ref "IC6") (pin "7") (pinfunction "EP_7") (pintype "passive"))
      (node (ref "R17") (pin "2") (pinfunction "2_2") (pintype "passive"))
      (node (ref "R20") (pin "1") (pinfunction "1_1") (pintype "passive"))
      (node (ref "R21") (pin "1") (pinfunction "1_1") (pintype "passive"))
      (node (ref "R22") (pin "1") (pinfunction "1_1") (pintype "passive"))
      (node (ref "R5") (pin "2") (pinfunction "2_2") (pintype "passive"))
      (node (ref "R6") (pin "2") (pinfunction "2_2") (pintype "passive"))
      (node (ref "R7") (pin "2") (pinfunction "2_2") (pintype "passive"))
      (node (ref "SW1") (pin "1") (pinfunction "1_1") (pintype "passive"))
      (node (ref "SW2") (pin "1") (pinfunction "1_1") (pintype "passive"))
      (node (ref "SW3") (pin "1") (pinfunction "1_1") (pintype "passive"))
      (node (ref "X2") (pin "3") (pinfunction "3_3") (pintype "power_in"))
    )
    (net (code "28") (name "Net-(BT1-+)") (class "Default")
      (node (ref "BT1") (pin "1") (pinfunction "+_1") (pintype "passive"))
      (node (ref "IC2") (pin "3") (pinfunction "VBAT_3") (pintype "power_in"))
    )
    (net (code "29") (name "Net-(C1-Pad2)") (class "Default")
      (node (ref "C1") (pin "2") (pinfunction "2_2") (pintype "passive"))
      (node (ref "R3") (pin "2") (pinfunction "2_2") (pintype "passive"))
      (node (ref "R4") (pin "2") (pinfunction "2_2") (pintype "passive"))
    )
    (net (code "30") (name "Net-(CN1-CTTD)") (class "Default")
      (node (ref "C2") (pin "2") (pinfunction "2_2") (pintype "passive"))
      (node (ref "CN1") (pin "4") (pinfunction "CTTD_4") (pintype "passive"))
      (node (ref "FB1") (pin "2") (pinfunction "2_2") (pintype "passive"))
      (node (ref "R1") (pin "1") (pinfunction "1_1") (pintype "passive"))
      (node (ref "R2") (pin "1") (pinfunction "1_1") (pintype "passive"))
    )
    (net (code "31") (name "Net-(CN1-G-)") (class "Default")
      (node (ref "CN1") (pin "10") (pinfunction "G-_10") (pintype "passive"))
      (node (ref "R6") (pin "1") (pinfunction "1_1") (pintype "passive"))
    )
    (net (code "32") (name "Net-(CN1-Y-)") (class "Default")
      (node (ref "CN1") (pin "11") (pinfunction "Y-_11") (pintype "passive"))
      (node (ref "R5") (pin "1") (pinfunction "1_1") (pintype "passive"))
    )
    (net (code "33") (name "Net-(IC1-OSC1)") (class "Default")
      (node (ref "C5") (pin "2") (pinfunction "2_2") (pintype "passive"))
      (node (ref "IC1") (pin "23") (pinfunction "OSC1_23") (pintype "input"))
      (node (ref "X1") (pin "2") (pinfunction "2_2") (pintype "passive"))
    )
    (net (code "34") (name "Net-(IC1-OSC2)") (class "Default")
      (node (ref "C6") (pin "2") (pinfunction "2_2") (pintype "passive"))
      (node (ref "IC1") (pin "24") (pinfunction "OSC2_24") (pintype "output"))
      (node (ref "X1") (pin "1") (pinfunction "1_1") (pintype "passive"))
    )
    (net (code "35") (name "Net-(IC1-RBIAS)") (class "Default")
      (node (ref "IC1") (pin "14") (pinfunction "RBIAS_14") (pintype "input"))
      (node (ref "R7") (pin "1") (pinfunction "1_1") (pintype "passive"))
    )
    (net (code "36") (name "Net-(IC1-VCAP)") (class "Default")
      (node (ref "C7") (pin "2") (pinfunction "2_2") (pintype "passive"))
      (node (ref "IC1") (pin "1") (pinfunction "VCAP_1") (pintype "power_in"))
    )
    (net (code "37") (name "Net-(IC2-OSCI)") (class "Default")
      (node (ref "C13") (pin "2") (pinfunction "2_2") (pintype "passive"))
      (node (ref "IC2") (pin "1") (pinfunction "OSCI_1") (pintype "input"))
      (node (ref "X2") (pin "1") (pinfunction "1_1") (pintype "passive"))
    )
    (net (code "38") (name "Net-(IC2-OSCO)") (class "Default")
      (node (ref "C16") (pin "2") (pinfunction "2_2") (pintype "passive"))
      (node (ref "IC2") (pin "2") (pinfunction "OSCO_2") (pintype "output"))
      (node (ref "X2") (pin "2") (pinfunction "2_2") (pintype "passive"))
    )
    (net (code "39") (name "Net-(LED1-Pad1)") (class "Default")
      (node (ref "LED1") (pin "1") (pinfunction "1_1") (pintype "passive"))
      (node (ref "R17") (pin "1") (pinfunction "1_1") (pintype "passive"))
    )
    (net (code "40") (name "Net-(LED2-Pad1)") (class "Default")
      (node (ref "LED2") (pin "1") (pinfunction "1_1") (pintype "passive"))
      (node (ref "R20") (pin "2") (pinfunction "2_2") (pintype "passive"))
    )
    (net (code "41") (name "Net-(LED3-Pad1)") (class "Default")
      (node (ref "LED3") (pin "1") (pinfunction "1_1") (pintype "passive"))
      (node (ref "R21") (pin "2") (pinfunction "2_2") (pintype "passive"))
    )
    (net (code "42") (name "Net-(LED4-Pad1)") (class "Default")
      (node (ref "LED4") (pin "1") (pinfunction "1_1") (pintype "passive"))
      (node (ref "R22") (pin "2") (pinfunction "2_2") (pintype "passive"))
    )
    (net (code "43") (name "unconnected-(CN1-CTRD-Pad5)") (class "Default")
      (node (ref "CN1") (pin "5") (pinfunction "CTRD_5") (pintype "passive"))
    )
    (net (code "44") (name "unconnected-(CN4-DAT1{slash}NC-Pad8)") (class "Default")
      (node (ref "CN4") (pin "8") (pinfunction "DAT1/NC_8") (pintype "passive"))
    )
    (net (code "45") (name "unconnected-(CN4-DAT2{slash}NC-Pad1)") (class "Default")
      (node (ref "CN4") (pin "1") (pinfunction "DAT2/NC_1") (pintype "passive"))
    )
    (net (code "46") (name "unconnected-(CN5-Pad5)") (class "Default")
      (node (ref "CN5") (pin "5") (pinfunction "5_5") (pintype "passive"))
    )
    (net (code "47") (name "unconnected-(CN5-Pad6)") (class "Default")
      (node (ref "CN5") (pin "6") (pinfunction "6_6") (pintype "passive"))
    )
    (net (code "48") (name "unconnected-(CN6-Pad1)") (class "Default")
      (node (ref "CN6") (pin "1") (pinfunction "1_1") (pintype "passive"))
    )
    (net (code "49") (name "unconnected-(CN6-Pad2)") (class "Default")
      (node (ref "CN6") (pin "2") (pinfunction "2_2") (pintype "passive"))
    )
    (net (code "50") (name "unconnected-(CN6-Pad5)") (class "Default")
      (node (ref "CN6") (pin "5") (pinfunction "5_5") (pintype "passive"))
    )
    (net (code "51") (name "unconnected-(CN6-Pad6)") (class "Default")
      (node (ref "CN6") (pin "6") (pinfunction "6_6") (pintype "passive"))
    )
    (net (code "52") (name "unconnected-(IC1-CLKOUT-Pad3)") (class "Default")
      (node (ref "IC1") (pin "3") (pinfunction "CLKOUT_3") (pintype "output"))
    )
    (net (code "53") (name "unconnected-(IC1-NC-Pad5)") (class "Default")
      (node (ref "IC1") (pin "5") (pinfunction "NC_5") (pintype "passive"))
    )
    (net (code "54") (name "unconnected-(IC6-NC-Pad3)") (class "Default")
      (node (ref "IC6") (pin "3") (pinfunction "NC_3") (pintype "passive"))
    )
    (net (code "55") (name "unconnected-(IC6-NC-Pad4)") (class "Default")
      (node (ref "IC6") (pin "4") (pinfunction "NC_4") (pintype "passive"))
    )
  )
)
